# Eth_Switch.net
KiCad netlist of a schematic drawn in Altium Designer
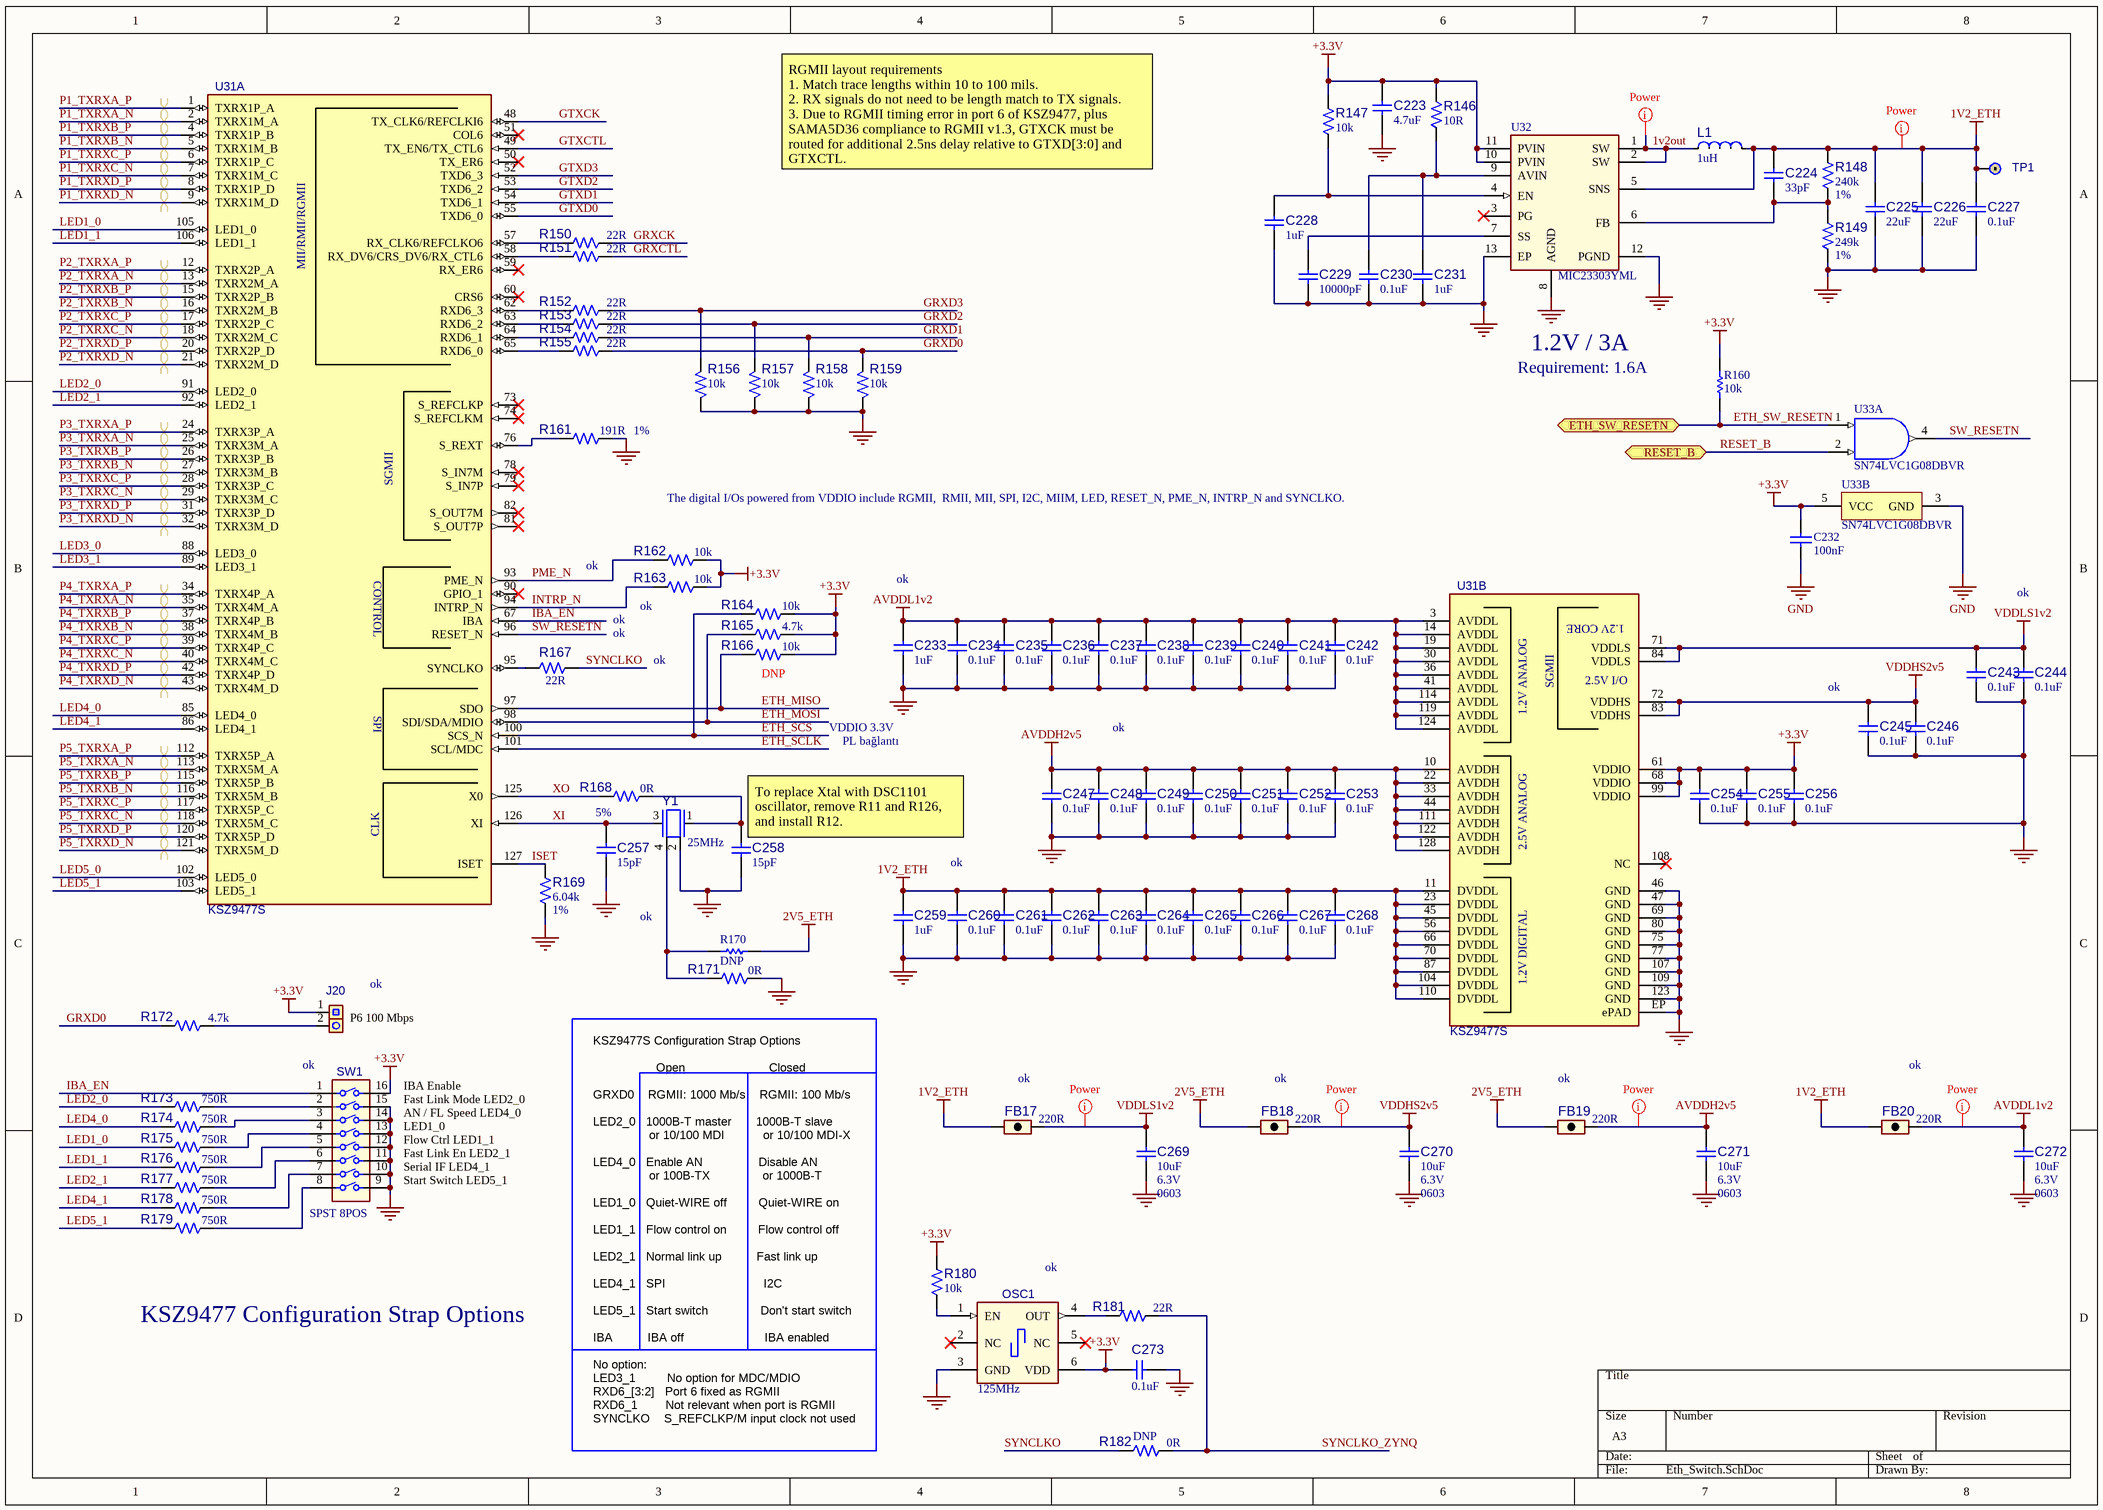
[diagram p0: Eth_Switch.SchDoc]

(export (version "E")
  (design (tool "Eeschema 10.0.6"))
  (components
    (comp (ref "C223")
      (value "4.7uF")
      (footprint "Ultrascale_PcbLib:CAP_C_0603")
      (description "Capacitor")
      (fields
        (field (name "VOLTAGE") "16V")
        (field (name "TOLERANCE") "10%")
        (field (name "OWNER") "Jairuz Agang-ang")
      )
      (libsource (lib "Ultrascale_SchLib") (part "Capacitor NP"))
    )
    (comp (ref "C224")
      (value "33pF")
      (footprint "Ultrascale_PcbLib:CAP_C_0603")
      (description "Capacitor")
      (fields (field (name "VOLTAGE") "50V") (field (name "TOLERANCE") "5%"))
      (libsource (lib "Ultrascale_SchLib") (part "Capacitor NP"))
    )
    (comp (ref "C225")
      (value "22uF")
      (footprint "Ultrascale_PcbLib:CAP_C_0805")
      (description "Capacitor")
      (fields (field (name "VOLTAGE") "16V") (field (name "TOLERANCE") "10%"))
      (libsource (lib "Ultrascale_SchLib") (part "Capacitor NP"))
    )
    (comp (ref "C226")
      (value "22uF")
      (footprint "Ultrascale_PcbLib:CAP_C_0805")
      (description "Capacitor")
      (fields (field (name "VOLTAGE") "16V") (field (name "TOLERANCE") "10%"))
      (libsource (lib "Ultrascale_SchLib") (part "Capacitor NP"))
    )
    (comp (ref "C227")
      (value "0.1uF")
      (footprint "Ultrascale_PcbLib:CAP_C_0402")
      (description "Capacitor")
      (fields
        (field (name "VOLTAGE") "50V")
        (field (name "TOLERANCE") "10%")
        (field (name "OWNER") "Jamus Griego")
      )
      (libsource (lib "Ultrascale_SchLib") (part "Capacitor NP"))
    )
    (comp (ref "C228")
      (value "1uF")
      (footprint "Ultrascale_PcbLib:CAP_C_0402")
      (description "Capacitor")
      (fields
        (field (name "VOLTAGE") "16V")
        (field (name "TOLERANCE") "10%")
        (field (name "OWNER") "Tad Ahlvers")
      )
      (libsource (lib "Ultrascale_SchLib") (part "Capacitor NP"))
    )
    (comp (ref "C229")
      (value "10000pF")
      (footprint "Ultrascale_PcbLib:CAP_C_0402")
      (description "Capacitor")
      (fields (field (name "VOLTAGE") "16V") (field (name "TOLERANCE") "10%"))
      (libsource (lib "Ultrascale_SchLib") (part "Capacitor NP"))
    )
    (comp (ref "C230")
      (value "0.1uF")
      (footprint "Ultrascale_PcbLib:CAP_C_0402")
      (description "Capacitor")
      (fields
        (field (name "VOLTAGE") "50V")
        (field (name "TOLERANCE") "10%")
        (field (name "OWNER") "Jamus Griego")
      )
      (libsource (lib "Ultrascale_SchLib") (part "Capacitor NP"))
    )
    (comp (ref "C231")
      (value "1uF")
      (footprint "Ultrascale_PcbLib:CAP_C_0402")
      (description "Capacitor")
      (fields
        (field (name "VOLTAGE") "16V")
        (field (name "TOLERANCE") "10%")
        (field (name "OWNER") "Tad Ahlvers")
      )
      (libsource (lib "Ultrascale_SchLib") (part "Capacitor NP"))
    )
    (comp (ref "C232")
      (value "100nF")
      (footprint "CAPC1005L_0402")
      (description "CAP CER 0.1UF 25V X7R 0402")
      (fields (field (name "VOLTAGE") "25V") (field (name "TOLERANCE") "10%"))
      (libsource (lib "Ultrascale_SchLib") (part "CAPCER0402X7R100N25V_10T"))
    )
    (comp (ref "C233")
      (value "1uF")
      (footprint "Ultrascale_PcbLib:CAP_C_0402")
      (description "Capacitor")
      (fields
        (field (name "VOLTAGE") "16V")
        (field (name "TOLERANCE") "10%")
        (field (name "OWNER") "Tad Ahlvers")
      )
      (libsource (lib "Ultrascale_SchLib") (part "Capacitor NP"))
    )
    (comp (ref "C234")
      (value "0.1uF")
      (footprint "Ultrascale_PcbLib:CAP_C_0402")
      (description "Capacitor")
      (fields
        (field (name "VOLTAGE") "50V")
        (field (name "TOLERANCE") "10%")
        (field (name "OWNER") "Jamus Griego")
      )
      (libsource (lib "Ultrascale_SchLib") (part "Capacitor NP"))
    )
    (comp (ref "C235")
      (value "0.1uF")
      (footprint "Ultrascale_PcbLib:CAP_C_0402")
      (description "Capacitor")
      (fields
        (field (name "VOLTAGE") "50V")
        (field (name "TOLERANCE") "10%")
        (field (name "OWNER") "Jamus Griego")
      )
      (libsource (lib "Ultrascale_SchLib") (part "Capacitor NP"))
    )
    (comp (ref "C236")
      (value "0.1uF")
      (footprint "Ultrascale_PcbLib:CAP_C_0402")
      (description "Capacitor")
      (fields
        (field (name "VOLTAGE") "50V")
        (field (name "TOLERANCE") "10%")
        (field (name "OWNER") "Jamus Griego")
      )
      (libsource (lib "Ultrascale_SchLib") (part "Capacitor NP"))
    )
    (comp (ref "C237")
      (value "0.1uF")
      (footprint "Ultrascale_PcbLib:CAP_C_0402")
      (description "Capacitor")
      (fields
        (field (name "VOLTAGE") "50V")
        (field (name "TOLERANCE") "10%")
        (field (name "OWNER") "Jamus Griego")
      )
      (libsource (lib "Ultrascale_SchLib") (part "Capacitor NP"))
    )
    (comp (ref "C238")
      (value "0.1uF")
      (footprint "Ultrascale_PcbLib:CAP_C_0402")
      (description "Capacitor")
      (fields
        (field (name "VOLTAGE") "50V")
        (field (name "TOLERANCE") "10%")
        (field (name "OWNER") "Jamus Griego")
      )
      (libsource (lib "Ultrascale_SchLib") (part "Capacitor NP"))
    )
    (comp (ref "C239")
      (value "0.1uF")
      (footprint "Ultrascale_PcbLib:CAP_C_0402")
      (description "Capacitor")
      (fields
        (field (name "VOLTAGE") "50V")
        (field (name "TOLERANCE") "10%")
        (field (name "OWNER") "Jamus Griego")
      )
      (libsource (lib "Ultrascale_SchLib") (part "Capacitor NP"))
    )
    (comp (ref "C240")
      (value "0.1uF")
      (footprint "Ultrascale_PcbLib:CAP_C_0402")
      (description "Capacitor")
      (fields
        (field (name "VOLTAGE") "50V")
        (field (name "TOLERANCE") "10%")
        (field (name "OWNER") "Jamus Griego")
      )
      (libsource (lib "Ultrascale_SchLib") (part "Capacitor NP"))
    )
    (comp (ref "C241")
      (value "0.1uF")
      (footprint "Ultrascale_PcbLib:CAP_C_0402")
      (description "Capacitor")
      (fields
        (field (name "VOLTAGE") "50V")
        (field (name "TOLERANCE") "10%")
        (field (name "OWNER") "Jamus Griego")
      )
      (libsource (lib "Ultrascale_SchLib") (part "Capacitor NP"))
    )
    (comp (ref "C242")
      (value "0.1uF")
      (footprint "Ultrascale_PcbLib:CAP_C_0402")
      (description "Capacitor")
      (fields
        (field (name "VOLTAGE") "50V")
        (field (name "TOLERANCE") "10%")
        (field (name "OWNER") "Jamus Griego")
      )
      (libsource (lib "Ultrascale_SchLib") (part "Capacitor NP"))
    )
    (comp (ref "C243")
      (value "0.1uF")
      (footprint "Ultrascale_PcbLib:CAP_C_0402")
      (description "Capacitor")
      (fields
        (field (name "VOLTAGE") "50V")
        (field (name "TOLERANCE") "10%")
        (field (name "OWNER") "Jamus Griego")
      )
      (libsource (lib "Ultrascale_SchLib") (part "Capacitor NP"))
    )
    (comp (ref "C244")
      (value "0.1uF")
      (footprint "Ultrascale_PcbLib:CAP_C_0402")
      (description "Capacitor")
      (fields
        (field (name "VOLTAGE") "50V")
        (field (name "TOLERANCE") "10%")
        (field (name "OWNER") "Jamus Griego")
      )
      (libsource (lib "Ultrascale_SchLib") (part "Capacitor NP"))
    )
    (comp (ref "C245")
      (value "0.1uF")
      (footprint "Ultrascale_PcbLib:CAP_C_0402")
      (description "Capacitor")
      (fields
        (field (name "VOLTAGE") "50V")
        (field (name "TOLERANCE") "10%")
        (field (name "OWNER") "Jamus Griego")
      )
      (libsource (lib "Ultrascale_SchLib") (part "Capacitor NP"))
    )
    (comp (ref "C246")
      (value "0.1uF")
      (footprint "Ultrascale_PcbLib:CAP_C_0402")
      (description "Capacitor")
      (fields
        (field (name "VOLTAGE") "50V")
        (field (name "TOLERANCE") "10%")
        (field (name "OWNER") "Jamus Griego")
      )
      (libsource (lib "Ultrascale_SchLib") (part "Capacitor NP"))
    )
    (comp (ref "C247")
      (value "0.1uF")
      (footprint "Ultrascale_PcbLib:CAP_C_0402")
      (description "Capacitor")
      (fields
        (field (name "VOLTAGE") "50V")
        (field (name "TOLERANCE") "10%")
        (field (name "OWNER") "Jamus Griego")
      )
      (libsource (lib "Ultrascale_SchLib") (part "Capacitor NP"))
    )
    (comp (ref "C248")
      (value "0.1uF")
      (footprint "Ultrascale_PcbLib:CAP_C_0402")
      (description "Capacitor")
      (fields
        (field (name "VOLTAGE") "50V")
        (field (name "TOLERANCE") "10%")
        (field (name "OWNER") "Jamus Griego")
      )
      (libsource (lib "Ultrascale_SchLib") (part "Capacitor NP"))
    )
    (comp (ref "C249")
      (value "0.1uF")
      (footprint "Ultrascale_PcbLib:CAP_C_0402")
      (description "Capacitor")
      (fields
        (field (name "VOLTAGE") "50V")
        (field (name "TOLERANCE") "10%")
        (field (name "OWNER") "Jamus Griego")
      )
      (libsource (lib "Ultrascale_SchLib") (part "Capacitor NP"))
    )
    (comp (ref "C250")
      (value "0.1uF")
      (footprint "Ultrascale_PcbLib:CAP_C_0402")
      (description "Capacitor")
      (fields
        (field (name "VOLTAGE") "50V")
        (field (name "TOLERANCE") "10%")
        (field (name "OWNER") "Jamus Griego")
      )
      (libsource (lib "Ultrascale_SchLib") (part "Capacitor NP"))
    )
    (comp (ref "C251")
      (value "0.1uF")
      (footprint "Ultrascale_PcbLib:CAP_C_0402")
      (description "Capacitor")
      (fields
        (field (name "VOLTAGE") "50V")
        (field (name "TOLERANCE") "10%")
        (field (name "OWNER") "Jamus Griego")
      )
      (libsource (lib "Ultrascale_SchLib") (part "Capacitor NP"))
    )
    (comp (ref "C252")
      (value "0.1uF")
      (footprint "Ultrascale_PcbLib:CAP_C_0402")
      (description "Capacitor")
      (fields
        (field (name "VOLTAGE") "50V")
        (field (name "TOLERANCE") "10%")
        (field (name "OWNER") "Jamus Griego")
      )
      (libsource (lib "Ultrascale_SchLib") (part "Capacitor NP"))
    )
    (comp (ref "C253")
      (value "0.1uF")
      (footprint "Ultrascale_PcbLib:CAP_C_0402")
      (description "Capacitor")
      (fields
        (field (name "VOLTAGE") "50V")
        (field (name "TOLERANCE") "10%")
        (field (name "OWNER") "Jamus Griego")
      )
      (libsource (lib "Ultrascale_SchLib") (part "Capacitor NP"))
    )
    (comp (ref "C254")
      (value "0.1uF")
      (footprint "Ultrascale_PcbLib:CAP_C_0402")
      (description "Capacitor")
      (fields
        (field (name "VOLTAGE") "50V")
        (field (name "TOLERANCE") "10%")
        (field (name "OWNER") "Jamus Griego")
      )
      (libsource (lib "Ultrascale_SchLib") (part "Capacitor NP"))
    )
    (comp (ref "C255")
      (value "0.1uF")
      (footprint "Ultrascale_PcbLib:CAP_C_0402")
      (description "Capacitor")
      (fields
        (field (name "VOLTAGE") "50V")
        (field (name "TOLERANCE") "10%")
        (field (name "OWNER") "Jamus Griego")
      )
      (libsource (lib "Ultrascale_SchLib") (part "Capacitor NP"))
    )
    (comp (ref "C256")
      (value "0.1uF")
      (footprint "Ultrascale_PcbLib:CAP_C_0402")
      (description "Capacitor")
      (fields
        (field (name "VOLTAGE") "50V")
        (field (name "TOLERANCE") "10%")
        (field (name "OWNER") "Jamus Griego")
      )
      (libsource (lib "Ultrascale_SchLib") (part "Capacitor NP"))
    )
    (comp (ref "C257")
      (value "15pF")
      (footprint "Ultrascale_PcbLib:CAP_C_0402")
      (description "Capacitor")
      (fields
        (field (name "VOLTAGE") "50V")
        (field (name "TOLERANCE") "5%")
        (field (name "Comment") "Capacitor NP")
      )
      (libsource (lib "Ultrascale_SchLib") (part "Capacitor NP"))
    )
    (comp (ref "C258")
      (value "15pF")
      (footprint "Ultrascale_PcbLib:CAP_C_0402")
      (description "Capacitor")
      (fields (field (name "VOLTAGE") "50V") (field (name "TOLERANCE") "5%"))
      (libsource (lib "Ultrascale_SchLib") (part "Capacitor NP"))
    )
    (comp (ref "C259")
      (value "1uF")
      (footprint "Ultrascale_PcbLib:CAP_C_0402")
      (description "Capacitor")
      (fields
        (field (name "VOLTAGE") "16V")
        (field (name "TOLERANCE") "10%")
        (field (name "OWNER") "Tad Ahlvers")
      )
      (libsource (lib "Ultrascale_SchLib") (part "Capacitor NP"))
    )
    (comp (ref "C260")
      (value "0.1uF")
      (footprint "Ultrascale_PcbLib:CAP_C_0402")
      (description "Capacitor")
      (fields
        (field (name "VOLTAGE") "50V")
        (field (name "TOLERANCE") "10%")
        (field (name "OWNER") "Jamus Griego")
      )
      (libsource (lib "Ultrascale_SchLib") (part "Capacitor NP"))
    )
    (comp (ref "C261")
      (value "0.1uF")
      (footprint "Ultrascale_PcbLib:CAP_C_0402")
      (description "Capacitor")
      (fields
        (field (name "VOLTAGE") "50V")
        (field (name "TOLERANCE") "10%")
        (field (name "OWNER") "Jamus Griego")
      )
      (libsource (lib "Ultrascale_SchLib") (part "Capacitor NP"))
    )
    (comp (ref "C262")
      (value "0.1uF")
      (footprint "Ultrascale_PcbLib:CAP_C_0402")
      (description "Capacitor")
      (fields
        (field (name "VOLTAGE") "50V")
        (field (name "TOLERANCE") "10%")
        (field (name "OWNER") "Jamus Griego")
      )
      (libsource (lib "Ultrascale_SchLib") (part "Capacitor NP"))
    )
    (comp (ref "C263")
      (value "0.1uF")
      (footprint "Ultrascale_PcbLib:CAP_C_0402")
      (description "Capacitor")
      (fields
        (field (name "VOLTAGE") "50V")
        (field (name "TOLERANCE") "10%")
        (field (name "OWNER") "Jamus Griego")
      )
      (libsource (lib "Ultrascale_SchLib") (part "Capacitor NP"))
    )
    (comp (ref "C264")
      (value "0.1uF")
      (footprint "Ultrascale_PcbLib:CAP_C_0402")
      (description "Capacitor")
      (fields
        (field (name "VOLTAGE") "50V")
        (field (name "TOLERANCE") "10%")
        (field (name "OWNER") "Jamus Griego")
      )
      (libsource (lib "Ultrascale_SchLib") (part "Capacitor NP"))
    )
    (comp (ref "C265")
      (value "0.1uF")
      (footprint "Ultrascale_PcbLib:CAP_C_0402")
      (description "Capacitor")
      (fields
        (field (name "VOLTAGE") "50V")
        (field (name "TOLERANCE") "10%")
        (field (name "OWNER") "Jamus Griego")
      )
      (libsource (lib "Ultrascale_SchLib") (part "Capacitor NP"))
    )
    (comp (ref "C266")
      (value "0.1uF")
      (footprint "Ultrascale_PcbLib:CAP_C_0402")
      (description "Capacitor")
      (fields
        (field (name "VOLTAGE") "50V")
        (field (name "TOLERANCE") "10%")
        (field (name "OWNER") "Jamus Griego")
      )
      (libsource (lib "Ultrascale_SchLib") (part "Capacitor NP"))
    )
    (comp (ref "C267")
      (value "0.1uF")
      (footprint "Ultrascale_PcbLib:CAP_C_0402")
      (description "Capacitor")
      (fields
        (field (name "VOLTAGE") "50V")
        (field (name "TOLERANCE") "10%")
        (field (name "OWNER") "Jamus Griego")
      )
      (libsource (lib "Ultrascale_SchLib") (part "Capacitor NP"))
    )
    (comp (ref "C268")
      (value "0.1uF")
      (footprint "Ultrascale_PcbLib:CAP_C_0402")
      (description "Capacitor")
      (fields
        (field (name "VOLTAGE") "50V")
        (field (name "TOLERANCE") "10%")
        (field (name "OWNER") "Jamus Griego")
      )
      (libsource (lib "Ultrascale_SchLib") (part "Capacitor NP"))
    )
    (comp (ref "C269")
      (value "10uF")
      (footprint "Ultrascale_PcbLib:CAP_C_0603")
      (description "Capacitor")
      (fields
        (field (name "VOLTAGE") "6.3V")
        (field (name "PACKAGE") "0603")
        (field (name "TOLERANCE") "20%")
        (field (name "Comment") "Capacitor NP")
      )
      (libsource (lib "Ultrascale_SchLib") (part "Capacitor NP"))
    )
    (comp (ref "C270")
      (value "10uF")
      (footprint "Ultrascale_PcbLib:CAP_C_0603")
      (description "Capacitor")
      (fields
        (field (name "VOLTAGE") "6.3V")
        (field (name "PACKAGE") "0603")
        (field (name "TOLERANCE") "20%")
        (field (name "Comment") "Capacitor NP")
      )
      (libsource (lib "Ultrascale_SchLib") (part "Capacitor NP"))
    )
    (comp (ref "C271")
      (value "10uF")
      (footprint "Ultrascale_PcbLib:CAP_C_0603")
      (description "Capacitor")
      (fields
        (field (name "VOLTAGE") "6.3V")
        (field (name "PACKAGE") "0603")
        (field (name "TOLERANCE") "20%")
        (field (name "Comment") "Capacitor NP")
      )
      (libsource (lib "Ultrascale_SchLib") (part "Capacitor NP"))
    )
    (comp (ref "C272")
      (value "10uF")
      (footprint "Ultrascale_PcbLib:CAP_C_0603")
      (description "Capacitor")
      (fields
        (field (name "VOLTAGE") "6.3V")
        (field (name "PACKAGE") "0603")
        (field (name "TOLERANCE") "20%")
        (field (name "Comment") "Capacitor NP")
      )
      (libsource (lib "Ultrascale_SchLib") (part "Capacitor NP"))
    )
    (comp (ref "C273")
      (value "0.1uF")
      (footprint "Ultrascale_PcbLib:CAP_C_0402")
      (description "Capacitor")
      (fields
        (field (name "VOLTAGE") "50V")
        (field (name "TOLERANCE") "10%")
        (field (name "OWNER") "Jamus Griego")
      )
      (libsource (lib "Ultrascale_SchLib") (part "Capacitor NP"))
    )
    (comp (ref "FB17")
      (value "220R")
      (footprint "Ultrascale_PcbLib:IND_C_0603")
      (fields (field (name "Comment") "Ferrite Bead") (field (name "OWNER") "Razvan Cristescu"))
      (libsource (lib "Ultrascale_SchLib") (part "Ferrite Bead"))
    )
    (comp (ref "FB18")
      (value "220R")
      (footprint "Ultrascale_PcbLib:IND_C_0603")
      (fields (field (name "Comment") "Ferrite Bead") (field (name "OWNER") "Razvan Cristescu"))
      (libsource (lib "Ultrascale_SchLib") (part "Ferrite Bead"))
    )
    (comp (ref "FB19")
      (value "220R")
      (footprint "Ultrascale_PcbLib:IND_C_0603")
      (fields (field (name "Comment") "Ferrite Bead") (field (name "OWNER") "Razvan Cristescu"))
      (libsource (lib "Ultrascale_SchLib") (part "Ferrite Bead"))
    )
    (comp (ref "FB20")
      (value "220R")
      (footprint "Ultrascale_PcbLib:IND_C_0603")
      (fields (field (name "Comment") "Ferrite Bead") (field (name "OWNER") "Razvan Cristescu"))
      (libsource (lib "Ultrascale_SchLib") (part "Ferrite Bead"))
    )
    (comp (ref "J20")
      (value "HDR-2.54 Male 1x2")
      (footprint "Ultrascale_PcbLib:HDR_M_2.54_1x2")
      (description "CONN HEADER 2POS .100\" SGL GOLD")
      (fields
        (field (name "PART CHECKED") "Jennifer Hancock")
        (field (name "PART 3D MODEL CHECKED") "Jennifer Hancock")
        (field (name "OWNER") "*")
      )
      (libsource (lib "Ultrascale_SchLib") (part "Header 1x2"))
    )
    (comp (ref "L1")
      (value "1uH")
      (footprint "Ultrascale_PcbLib:IND_TAI_NR_L3W3H1.5")
      (description "Inductor")
      (fields (field (name "OWNER") "Tad Ahlvers"))
      (libsource (lib "Ultrascale_SchLib") (part "Inductor"))
    )
    (comp (ref "OSC1")
      (value "~")
      (footprint "Ultrascale_PcbLib:OSC_5MX3M2_A")
      (description "OSC MEMS 125.000MHZ CMOS SMD")
      (fields (field (name "FREQUENCY") "125MHz"))
      (libsource (lib "Ultrascale_SchLib") (part "DSC1101B12-125.0000"))
    )
    (comp (ref "R146")
      (value "10R")
      (footprint "Ultrascale_PcbLib:RES_C_0603")
      (description "Resistor")
      (fields
        (field (name "TOLERANCE") "1%")
        (field (name "VOLTAGE") "50V")
        (field (name "OWNER") "Aaron VanDuerm")
      )
      (libsource (lib "Ultrascale_SchLib") (part "Resistor"))
    )
    (comp (ref "R147")
      (value "10k")
      (footprint "Ultrascale_PcbLib:RES_C_0603")
      (description "Resistor")
      (fields (field (name "TOLERANCE") "1%") (field (name "POWER") "1/10W"))
      (libsource (lib "Ultrascale_SchLib") (part "Resistor"))
    )
    (comp (ref "R148")
      (value "240k")
      (footprint "Ultrascale_PcbLib:RES_C_0603")
      (description "Resistor")
      (fields
        (field (name "TOLERANCE") "1%")
        (field (name "VOLTAGE") "75V")
        (field (name "POWER") "1/10W")
        (field (name "OWNER") "Tad Ahlvers")
      )
      (libsource (lib "Ultrascale_SchLib") (part "Resistor"))
    )
    (comp (ref "R149")
      (value "249k")
      (footprint "Ultrascale_PcbLib:RES_C_0603")
      (description "Resistor")
      (fields (field (name "TOLERANCE") "1%") (field (name "VOLTAGE") "75V") (field (name "POWER") "1/10W"))
      (libsource (lib "Ultrascale_SchLib") (part "Resistor"))
    )
    (comp (ref "R150")
      (value "22R")
      (footprint "Ultrascale_PcbLib:RES_C_0603")
      (description "Resistor")
      (fields (field (name "TOLERANCE") "1%") (field (name "VOLTAGE") "50V"))
      (libsource (lib "Ultrascale_SchLib") (part "Resistor"))
    )
    (comp (ref "R151")
      (value "22R")
      (footprint "Ultrascale_PcbLib:RES_C_0603")
      (description "Resistor")
      (fields (field (name "TOLERANCE") "1%") (field (name "VOLTAGE") "50V"))
      (libsource (lib "Ultrascale_SchLib") (part "Resistor"))
    )
    (comp (ref "R152")
      (value "22R")
      (footprint "Ultrascale_PcbLib:RES_C_0603")
      (description "Resistor")
      (fields (field (name "TOLERANCE") "1%") (field (name "VOLTAGE") "50V"))
      (libsource (lib "Ultrascale_SchLib") (part "Resistor"))
    )
    (comp (ref "R153")
      (value "22R")
      (footprint "Ultrascale_PcbLib:RES_C_0603")
      (description "Resistor")
      (fields (field (name "TOLERANCE") "1%") (field (name "VOLTAGE") "50V"))
      (libsource (lib "Ultrascale_SchLib") (part "Resistor"))
    )
    (comp (ref "R154")
      (value "22R")
      (footprint "Ultrascale_PcbLib:RES_C_0603")
      (description "Resistor")
      (fields (field (name "TOLERANCE") "1%") (field (name "VOLTAGE") "50V"))
      (libsource (lib "Ultrascale_SchLib") (part "Resistor"))
    )
    (comp (ref "R155")
      (value "22R")
      (footprint "Ultrascale_PcbLib:RES_C_0603")
      (description "Resistor")
      (fields (field (name "TOLERANCE") "1%") (field (name "VOLTAGE") "50V"))
      (libsource (lib "Ultrascale_SchLib") (part "Resistor"))
    )
    (comp (ref "R156")
      (value "10k")
      (footprint "Ultrascale_PcbLib:RES_C_0603")
      (description "Resistor")
      (fields (field (name "TOLERANCE") "1%") (field (name "POWER") "1/10W"))
      (libsource (lib "Ultrascale_SchLib") (part "Resistor"))
    )
    (comp (ref "R157")
      (value "10k")
      (footprint "Ultrascale_PcbLib:RES_C_0603")
      (description "Resistor")
      (fields (field (name "TOLERANCE") "1%") (field (name "POWER") "1/10W"))
      (libsource (lib "Ultrascale_SchLib") (part "Resistor"))
    )
    (comp (ref "R158")
      (value "10k")
      (footprint "Ultrascale_PcbLib:RES_C_0603")
      (description "Resistor")
      (fields (field (name "TOLERANCE") "1%") (field (name "POWER") "1/10W"))
      (libsource (lib "Ultrascale_SchLib") (part "Resistor"))
    )
    (comp (ref "R159")
      (value "10k")
      (footprint "Ultrascale_PcbLib:RES_C_0603")
      (description "Resistor")
      (fields (field (name "TOLERANCE") "1%") (field (name "POWER") "1/10W"))
      (libsource (lib "Ultrascale_SchLib") (part "Resistor"))
    )
    (comp (ref "R160")
      (value "10k")
      (footprint "RESC1005L_0402")
      (description "RES SMD 10K OHM 0.5% 1/16W 0402")
      (fields (field (name "POWER") "1/16W") (field (name "TOLERANCE") "0.5%"))
      (libsource (lib "Ultrascale_SchLib") (part "RES0402_10K_0W1_05T"))
    )
    (comp (ref "R161")
      (value "191R")
      (footprint "Ultrascale_PcbLib:RES_C_0603")
      (description "Resistor")
      (fields
        (field (name "TOLERANCE") "1%")
        (field (name "POWER") "1/10W")
        (field (name "OWNER") "Sam Charles")
      )
      (libsource (lib "Ultrascale_SchLib") (part "Resistor"))
    )
    (comp (ref "R162")
      (value "10k")
      (footprint "Ultrascale_PcbLib:RES_C_0603")
      (description "Resistor")
      (fields (field (name "TOLERANCE") "1%") (field (name "POWER") "1/10W"))
      (libsource (lib "Ultrascale_SchLib") (part "Resistor"))
    )
    (comp (ref "R163")
      (value "10k")
      (footprint "Ultrascale_PcbLib:RES_C_0603")
      (description "Resistor")
      (fields (field (name "TOLERANCE") "1%") (field (name "POWER") "1/10W"))
      (libsource (lib "Ultrascale_SchLib") (part "Resistor"))
    )
    (comp (ref "R164")
      (value "10k")
      (footprint "Ultrascale_PcbLib:RES_C_0603")
      (description "Resistor")
      (fields (field (name "TOLERANCE") "1%") (field (name "POWER") "1/10W"))
      (libsource (lib "Ultrascale_SchLib") (part "Resistor"))
    )
    (comp (ref "R165")
      (value "4.7k")
      (footprint "Ultrascale_PcbLib:RES_C_0603")
      (description "Resistor")
      (fields (field (name "TOLERANCE") "1%") (field (name "VOLTAGE") "50V"))
      (libsource (lib "Ultrascale_SchLib") (part "Resistor"))
    )
    (comp (ref "R166")
      (value "10k")
      (footprint "Ultrascale_PcbLib:RES_C_0603")
      (description "Resistor")
      (fields (field (name "TOLERANCE") "1%") (field (name "POWER") "1/10W") (field (name "POPULATED") "DNP"))
      (libsource (lib "Ultrascale_SchLib") (part "Resistor"))
    )
    (comp (ref "R167")
      (value "22R")
      (footprint "Ultrascale_PcbLib:RES_C_0603")
      (description "Resistor")
      (fields (field (name "TOLERANCE") "1%") (field (name "VOLTAGE") "50V"))
      (libsource (lib "Ultrascale_SchLib") (part "Resistor"))
    )
    (comp (ref "R168")
      (value "0R")
      (footprint "Ultrascale_PcbLib:RES_C_0603")
      (description "Resistor")
      (fields (field (name "POWER") "1/10W"))
      (libsource (lib "Ultrascale_SchLib") (part "Resistor"))
    )
    (comp (ref "R169")
      (value "6.04k")
      (footprint "Ultrascale_PcbLib:RES_C_0603")
      (description "Resistor")
      (fields (field (name "TOLERANCE") "1%") (field (name "VOLTAGE") "50V") (field (name "POWER") "1/10W"))
      (libsource (lib "Ultrascale_SchLib") (part "Resistor"))
    )
    (comp (ref "R170")
      (value "DNP")
      (footprint "RESC1005L_0402")
      (description "RES SMD 0402 Footprint")
      (fields (field (name "Comment") "RES0402"))
      (libsource (lib "Ultrascale_SchLib") (part "RES0402"))
    )
    (comp (ref "R171")
      (value "0R")
      (footprint "Ultrascale_PcbLib:RES_C_0603")
      (description "Resistor")
      (fields (field (name "POWER") "1/10W"))
      (libsource (lib "Ultrascale_SchLib") (part "Resistor"))
    )
    (comp (ref "R172")
      (value "4.7k")
      (footprint "Ultrascale_PcbLib:RES_C_0603")
      (description "Resistor")
      (fields (field (name "TOLERANCE") "1%") (field (name "VOLTAGE") "50V"))
      (libsource (lib "Ultrascale_SchLib") (part "Resistor"))
    )
    (comp (ref "R173")
      (value "750R")
      (footprint "Ultrascale_PcbLib:RES_C_0603")
      (description "Resistor")
      (fields
        (field (name "TOLERANCE") "1%")
        (field (name "VOLTAGE") "75V")
        (field (name "OWNER") "Tad Ahlvers")
      )
      (libsource (lib "Ultrascale_SchLib") (part "Resistor"))
    )
    (comp (ref "R174")
      (value "750R")
      (footprint "Ultrascale_PcbLib:RES_C_0603")
      (description "Resistor")
      (fields
        (field (name "TOLERANCE") "1%")
        (field (name "VOLTAGE") "75V")
        (field (name "OWNER") "Tad Ahlvers")
      )
      (libsource (lib "Ultrascale_SchLib") (part "Resistor"))
    )
    (comp (ref "R175")
      (value "750R")
      (footprint "Ultrascale_PcbLib:RES_C_0603")
      (description "Resistor")
      (fields
        (field (name "TOLERANCE") "1%")
        (field (name "VOLTAGE") "75V")
        (field (name "OWNER") "Tad Ahlvers")
      )
      (libsource (lib "Ultrascale_SchLib") (part "Resistor"))
    )
    (comp (ref "R176")
      (value "750R")
      (footprint "Ultrascale_PcbLib:RES_C_0603")
      (description "Resistor")
      (fields
        (field (name "TOLERANCE") "1%")
        (field (name "VOLTAGE") "75V")
        (field (name "OWNER") "Tad Ahlvers")
      )
      (libsource (lib "Ultrascale_SchLib") (part "Resistor"))
    )
    (comp (ref "R177")
      (value "750R")
      (footprint "Ultrascale_PcbLib:RES_C_0603")
      (description "Resistor")
      (fields
        (field (name "TOLERANCE") "1%")
        (field (name "VOLTAGE") "75V")
        (field (name "OWNER") "Tad Ahlvers")
      )
      (libsource (lib "Ultrascale_SchLib") (part "Resistor"))
    )
    (comp (ref "R178")
      (value "750R")
      (footprint "Ultrascale_PcbLib:RES_C_0603")
      (description "Resistor")
      (fields
        (field (name "TOLERANCE") "1%")
        (field (name "VOLTAGE") "75V")
        (field (name "OWNER") "Tad Ahlvers")
      )
      (libsource (lib "Ultrascale_SchLib") (part "Resistor"))
    )
    (comp (ref "R179")
      (value "750R")
      (footprint "Ultrascale_PcbLib:RES_C_0603")
      (description "Resistor")
      (fields
        (field (name "TOLERANCE") "1%")
        (field (name "VOLTAGE") "75V")
        (field (name "OWNER") "Tad Ahlvers")
      )
      (libsource (lib "Ultrascale_SchLib") (part "Resistor"))
    )
    (comp (ref "R180")
      (value "10k")
      (footprint "Ultrascale_PcbLib:RES_C_0603")
      (description "Resistor")
      (fields (field (name "TOLERANCE") "1%") (field (name "POWER") "1/10W"))
      (libsource (lib "Ultrascale_SchLib") (part "Resistor"))
    )
    (comp (ref "R181")
      (value "22R")
      (footprint "Ultrascale_PcbLib:RES_C_0603")
      (description "Resistor")
      (fields (field (name "TOLERANCE") "1%") (field (name "VOLTAGE") "50V"))
      (libsource (lib "Ultrascale_SchLib") (part "Resistor"))
    )
    (comp (ref "R182")
      (value "0R")
      (footprint "Ultrascale_PcbLib:RES_C_0603")
      (description "Resistor")
      (fields (field (name "POWER") "1/10W") (field (name "POPULATED") "DNP"))
      (libsource (lib "Ultrascale_SchLib") (part "Resistor"))
    )
    (comp (ref "SW1")
      (value "SPST 8POS")
      (footprint "Ultrascale_PcbLib:SW_SM_8POS24V_TE")
      (description "Switch DIP SPST 8POS SMD")
      (libsource (lib "Ultrascale_SchLib") (part "Switch DIP 8 Pos"))
    )
    (comp (ref "TP1")
      (value "Jumper")
      (footprint "Ultrascale_PcbLib:TP_PAD51D36")
      (description "Test Pad TH 51X36")
      (fields (field (name "MANUFACTURER PART NUMBER") "none"))
      (libsource (lib "Ultrascale_SchLib") (part "TEST PAD TH 51X36"))
    )
    (comp (ref "U31")
      (value "KSZ9477S")
      (footprint "TQFP-128_14x14_EP10x10")
      (description "IC, 7-Port Gigabit Ethernet Switch with 2 RGMII / MII / RMII Interfaces, TQFP128")
      (fields (field (name "OWNER") "sam charles"))
      (libsource (lib "Ultrascale_SchLib") (part "KSZ9477S_TQFP128"))
    )
    (comp (ref "U32")
      (value "MIC23303YML")
      (footprint "Ultrascale_PcbLib:DFN-12_3x3")
      (description "4MHz PWM 3A Buck Regulator with HyperLight Load and Power Good")
      (fields (field (name "OWNER") "*") (field (name "PART CHECKED") "Carl Johnson"))
      (libsource (lib "Ultrascale_SchLib") (part "MIC23303YML"))
    )
    (comp (ref "U33")
      (value "SN74LVC1G08DBVR")
      (footprint "DBV0005A_N")
      (description "Single 2-Input Positive-AND Gate, DBV0005A, LARGE T&R")
      (fields (field (name "GENERIC PART NUMBER") "SN74LVC1G08"))
      (libsource (lib "Ultrascale_SchLib") (part "SN74LVC1G08DBVR"))
    )
    (comp (ref "Y1")
      (value "XTAL 25MHz 4 pins 3225")
      (footprint "Ultrascale_PcbLib:XTAL_4PIN_3M2X2M5")
      (description "Crystal 25MHz 4 pins 3225")
      (fields (field (name "FREQUENCY") "25MHz"))
      (libsource (lib "Ultrascale_SchLib") (part "XTAL 25MHz 4 pins 3225"))
    )
  )
  (nets
    (net (code "1") (name "+3.3V") (class "Default")
      (node (ref "C223") (pin "2") (pinfunction "2_2") (pintype "passive"))
      (node (ref "C232") (pin "1") (pinfunction "1_1") (pintype "passive"))
      (node (ref "C254") (pin "2") (pinfunction "2_2") (pintype "passive"))
      (node (ref "C255") (pin "2") (pinfunction "2_2") (pintype "passive"))
      (node (ref "C256") (pin "2") (pinfunction "2_2") (pintype "passive"))
      (node (ref "C273") (pin "2") (pinfunction "2_2") (pintype "passive"))
      (node (ref "J20") (pin "1") (pinfunction "P1_1") (pintype "passive"))
      (node (ref "OSC1") (pin "6") (pinfunction "VDD_6") (pintype "power_in"))
      (node (ref "R146") (pin "2") (pinfunction "2_2") (pintype "passive"))
      (node (ref "R147") (pin "2") (pinfunction "2_2") (pintype "passive"))
      (node (ref "R160") (pin "2") (pinfunction "2_2") (pintype "passive"))
      (node (ref "R162") (pin "1") (pinfunction "1_1") (pintype "passive"))
      (node (ref "R163") (pin "1") (pinfunction "1_1") (pintype "passive"))
      (node (ref "R164") (pin "1") (pinfunction "1_1") (pintype "passive"))
      (node (ref "R165") (pin "1") (pinfunction "1_1") (pintype "passive"))
      (node (ref "R166") (pin "1") (pinfunction "1_1") (pintype "passive"))
      (node (ref "R180") (pin "2") (pinfunction "2_2") (pintype "passive"))
      (node (ref "SW1") (pin "16") (pinfunction "16_16") (pintype "passive"))
      (node (ref "U31") (pin "61") (pinfunction "VDDIO_61") (pintype "power_in"))
      (node (ref "U31") (pin "68") (pinfunction "VDDIO_68") (pintype "power_in"))
      (node (ref "U31") (pin "99") (pinfunction "VDDIO_99") (pintype "power_in"))
      (node (ref "U32") (pin "10") (pinfunction "PVIN_10") (pintype "power_in"))
      (node (ref "U32") (pin "11") (pinfunction "PVIN_11") (pintype "power_in"))
      (node (ref "U33") (pin "5") (pinfunction "VCC_5") (pintype "power_in"))
    )
    (net (code "2") (name "/1v2out") (class "Default")
      (node (ref "L1") (pin "1") (pinfunction "S_1") (pintype "passive"))
      (node (ref "U32") (pin "1") (pinfunction "SW_1") (pintype "passive"))
      (node (ref "U32") (pin "2") (pinfunction "SW_2") (pintype "passive"))
    )
    (net (code "3") (name "/ETH_MISO") (class "Default")
      (node (ref "R166") (pin "2") (pinfunction "2_2") (pintype "passive"))
      (node (ref "U31") (pin "97") (pinfunction "SDO_97") (pintype "output"))
    )
    (net (code "4") (name "/ETH_MOSI") (class "Default")
      (node (ref "R165") (pin "2") (pinfunction "2_2") (pintype "passive"))
      (node (ref "U31") (pin "98") (pinfunction "SDI/SDA/MDIO_98") (pintype "bidirectional"))
    )
    (net (code "5") (name "/ETH_SCLK") (class "Default")
      (node (ref "U31") (pin "101") (pinfunction "SCL/MDC_101") (pintype "input"))
    )
    (net (code "6") (name "/ETH_SCS") (class "Default")
      (node (ref "R164") (pin "2") (pinfunction "2_2") (pintype "passive"))
      (node (ref "U31") (pin "100") (pinfunction "SCS_N_100") (pintype "input"))
    )
    (net (code "7") (name "/ETH_SW_RESETN") (class "Default")
      (node (ref "R160") (pin "1") (pinfunction "1_1") (pintype "passive"))
      (node (ref "U33") (pin "1") (pinfunction "A_1") (pintype "input"))
    )
    (net (code "8") (name "/GRXCK") (class "Default")
      (node (ref "R150") (pin "2") (pinfunction "2_2") (pintype "passive"))
    )
    (net (code "9") (name "/GRXCTL") (class "Default")
      (node (ref "R151") (pin "2") (pinfunction "2_2") (pintype "passive"))
    )
    (net (code "10") (name "/GRXD0") (class "Default")
      (node (ref "R155") (pin "2") (pinfunction "2_2") (pintype "passive"))
      (node (ref "R159") (pin "1") (pinfunction "1_1") (pintype "passive"))
      (node (ref "R172") (pin "1") (pinfunction "1_1") (pintype "passive"))
    )
    (net (code "11") (name "/GRXD1") (class "Default")
      (node (ref "R154") (pin "2") (pinfunction "2_2") (pintype "passive"))
      (node (ref "R158") (pin "1") (pinfunction "1_1") (pintype "passive"))
    )
    (net (code "12") (name "/GRXD2") (class "Default")
      (node (ref "R153") (pin "2") (pinfunction "2_2") (pintype "passive"))
      (node (ref "R157") (pin "1") (pinfunction "1_1") (pintype "passive"))
    )
    (net (code "13") (name "/GRXD3") (class "Default")
      (node (ref "R152") (pin "2") (pinfunction "2_2") (pintype "passive"))
      (node (ref "R156") (pin "1") (pinfunction "1_1") (pintype "passive"))
    )
    (net (code "14") (name "/GTXCK") (class "Default")
      (node (ref "U31") (pin "48") (pinfunction "TX_CLK6/REFCLKI6_48") (pintype "bidirectional"))
    )
    (net (code "15") (name "/GTXCTL") (class "Default")
      (node (ref "U31") (pin "49") (pinfunction "TX_EN6/TX_CTL6_49") (pintype "input"))
    )
    (net (code "16") (name "/GTXD0") (class "Default")
      (node (ref "U31") (pin "55") (pinfunction "TXD6_0_55") (pintype "bidirectional"))
    )
    (net (code "17") (name "/GTXD1") (class "Default")
      (node (ref "U31") (pin "54") (pinfunction "TXD6_1_54") (pintype "input"))
    )
    (net (code "18") (name "/GTXD2") (class "Default")
      (node (ref "U31") (pin "53") (pinfunction "TXD6_2_53") (pintype "input"))
    )
    (net (code "19") (name "/GTXD3") (class "Default")
      (node (ref "U31") (pin "52") (pinfunction "TXD6_3_52") (pintype "input"))
    )
    (net (code "20") (name "/IBA_EN") (class "Default")
      (node (ref "SW1") (pin "1") (pinfunction "1_1") (pintype "passive"))
      (node (ref "U31") (pin "67") (pinfunction "IBA_67") (pintype "input"))
    )
    (net (code "21") (name "/INTRP_N") (class "Default")
      (node (ref "R163") (pin "2") (pinfunction "2_2") (pintype "passive"))
      (node (ref "U31") (pin "94") (pinfunction "INTRP_N_94") (pintype "output"))
    )
    (net (code "22") (name "/ISET") (class "Default")
      (node (ref "R169") (pin "2") (pinfunction "2_2") (pintype "passive"))
      (node (ref "U31") (pin "127") (pinfunction "ISET_127") (pintype "passive"))
    )
    (net (code "23") (name "/LED1_0") (class "Default")
      (node (ref "R175") (pin "1") (pinfunction "1_1") (pintype "passive"))
      (node (ref "U31") (pin "105") (pinfunction "LED1_0_105") (pintype "bidirectional"))
    )
    (net (code "24") (name "/LED1_1") (class "Default")
      (node (ref "R176") (pin "1") (pinfunction "1_1") (pintype "passive"))
      (node (ref "U31") (pin "106") (pinfunction "LED1_1_106") (pintype "bidirectional"))
    )
    (net (code "25") (name "/LED2_0") (class "Default")
      (node (ref "R173") (pin "1") (pinfunction "1_1") (pintype "passive"))
      (node (ref "U31") (pin "91") (pinfunction "LED2_0_91") (pintype "bidirectional"))
    )
    (net (code "26") (name "/LED2_1") (class "Default")
      (node (ref "R177") (pin "1") (pinfunction "1_1") (pintype "passive"))
      (node (ref "U31") (pin "92") (pinfunction "LED2_1_92") (pintype "bidirectional"))
    )
    (net (code "27") (name "/LED3_0") (class "Default")
      (node (ref "U31") (pin "88") (pinfunction "LED3_0_88") (pintype "bidirectional"))
    )
    (net (code "28") (name "/LED3_1") (class "Default")
      (node (ref "U31") (pin "89") (pinfunction "LED3_1_89") (pintype "bidirectional"))
    )
    (net (code "29") (name "/LED4_0") (class "Default")
      (node (ref "R174") (pin "1") (pinfunction "1_1") (pintype "passive"))
      (node (ref "U31") (pin "85") (pinfunction "LED4_0_85") (pintype "bidirectional"))
    )
    (net (code "30") (name "/LED4_1") (class "Default")
      (node (ref "R178") (pin "1") (pinfunction "1_1") (pintype "passive"))
      (node (ref "U31") (pin "86") (pinfunction "LED4_1_86") (pintype "bidirectional"))
    )
    (net (code "31") (name "/LED5_0") (class "Default")
      (node (ref "U31") (pin "102") (pinfunction "LED5_0_102") (pintype "bidirectional"))
    )
    (net (code "32") (name "/LED5_1") (class "Default")
      (node (ref "R179") (pin "1") (pinfunction "1_1") (pintype "passive"))
      (node (ref "U31") (pin "103") (pinfunction "LED5_1_103") (pintype "bidirectional"))
    )
    (net (code "33") (name "/P1_TXRXA_N") (class "Default")
      (node (ref "U31") (pin "2") (pinfunction "TXRX1M_A_2") (pintype "bidirectional"))
    )
    (net (code "34") (name "/P1_TXRXA_P") (class "Default")
      (node (ref "U31") (pin "1") (pinfunction "TXRX1P_A_1") (pintype "bidirectional"))
    )
    (net (code "35") (name "/P1_TXRXB_N") (class "Default")
      (node (ref "U31") (pin "5") (pinfunction "TXRX1M_B_5") (pintype "bidirectional"))
    )
    (net (code "36") (name "/P1_TXRXB_P") (class "Default")
      (node (ref "U31") (pin "4") (pinfunction "TXRX1P_B_4") (pintype "bidirectional"))
    )
    (net (code "37") (name "/P1_TXRXC_N") (class "Default")
      (node (ref "U31") (pin "7") (pinfunction "TXRX1M_C_7") (pintype "bidirectional"))
    )
    (net (code "38") (name "/P1_TXRXC_P") (class "Default")
      (node (ref "U31") (pin "6") (pinfunction "TXRX1P_C_6") (pintype "bidirectional"))
    )
    (net (code "39") (name "/P1_TXRXD_N") (class "Default")
      (node (ref "U31") (pin "9") (pinfunction "TXRX1M_D_9") (pintype "bidirectional"))
    )
    (net (code "40") (name "/P1_TXRXD_P") (class "Default")
      (node (ref "U31") (pin "8") (pinfunction "TXRX1P_D_8") (pintype "bidirectional"))
    )
    (net (code "41") (name "/P2_TXRXA_N") (class "Default")
      (node (ref "U31") (pin "13") (pinfunction "TXRX2M_A_13") (pintype "bidirectional"))
    )
    (net (code "42") (name "/P2_TXRXA_P") (class "Default")
      (node (ref "U31") (pin "12") (pinfunction "TXRX2P_A_12") (pintype "bidirectional"))
    )
    (net (code "43") (name "/P2_TXRXB_N") (class "Default")
      (node (ref "U31") (pin "16") (pinfunction "TXRX2M_B_16") (pintype "bidirectional"))
    )
    (net (code "44") (name "/P2_TXRXB_P") (class "Default")
      (node (ref "U31") (pin "15") (pinfunction "TXRX2P_B_15") (pintype "bidirectional"))
    )
    (net (code "45") (name "/P2_TXRXC_N") (class "Default")
      (node (ref "U31") (pin "18") (pinfunction "TXRX2M_C_18") (pintype "bidirectional"))
    )
    (net (code "46") (name "/P2_TXRXC_P") (class "Default")
      (node (ref "U31") (pin "17") (pinfunction "TXRX2P_C_17") (pintype "bidirectional"))
    )
    (net (code "47") (name "/P2_TXRXD_N") (class "Default")
      (node (ref "U31") (pin "21") (pinfunction "TXRX2M_D_21") (pintype "bidirectional"))
    )
    (net (code "48") (name "/P2_TXRXD_P") (class "Default")
      (node (ref "U31") (pin "20") (pinfunction "TXRX2P_D_20") (pintype "bidirectional"))
    )
    (net (code "49") (name "/P3_TXRXA_N") (class "Default")
      (node (ref "U31") (pin "25") (pinfunction "TXRX3M_A_25") (pintype "bidirectional"))
    )
    (net (code "50") (name "/P3_TXRXA_P") (class "Default")
      (node (ref "U31") (pin "24") (pinfunction "TXRX3P_A_24") (pintype "bidirectional"))
    )
    (net (code "51") (name "/P3_TXRXB_N") (class "Default")
      (node (ref "U31") (pin "27") (pinfunction "TXRX3M_B_27") (pintype "bidirectional"))
    )
    (net (code "52") (name "/P3_TXRXB_P") (class "Default")
      (node (ref "U31") (pin "26") (pinfunction "TXRX3P_B_26") (pintype "bidirectional"))
    )
    (net (code "53") (name "/P3_TXRXC_N") (class "Default")
      (node (ref "U31") (pin "29") (pinfunction "TXRX3M_C_29") (pintype "bidirectional"))
    )
    (net (code "54") (name "/P3_TXRXC_P") (class "Default")
      (node (ref "U31") (pin "28") (pinfunction "TXRX3P_C_28") (pintype "bidirectional"))
    )
    (net (code "55") (name "/P3_TXRXD_N") (class "Default")
      (node (ref "U31") (pin "32") (pinfunction "TXRX3M_D_32") (pintype "bidirectional"))
    )
    (net (code "56") (name "/P3_TXRXD_P") (class "Default")
      (node (ref "U31") (pin "31") (pinfunction "TXRX3P_D_31") (pintype "bidirectional"))
    )
    (net (code "57") (name "/P4_TXRXA_N") (class "Default")
      (node (ref "U31") (pin "35") (pinfunction "TXRX4M_A_35") (pintype "bidirectional"))
    )
    (net (code "58") (name "/P4_TXRXA_P") (class "Default")
      (node (ref "U31") (pin "34") (pinfunction "TXRX4P_A_34") (pintype "bidirectional"))
    )
    (net (code "59") (name "/P4_TXRXB_N") (class "Default")
      (node (ref "U31") (pin "38") (pinfunction "TXRX4M_B_38") (pintype "bidirectional"))
    )
    (net (code "60") (name "/P4_TXRXB_P") (class "Default")
      (node (ref "U31") (pin "37") (pinfunction "TXRX4P_B_37") (pintype "bidirectional"))
    )
    (net (code "61") (name "/P4_TXRXC_N") (class "Default")
      (node (ref "U31") (pin "40") (pinfunction "TXRX4M_C_40") (pintype "bidirectional"))
    )
    (net (code "62") (name "/P4_TXRXC_P") (class "Default")
      (node (ref "U31") (pin "39") (pinfunction "TXRX4P_C_39") (pintype "bidirectional"))
    )
    (net (code "63") (name "/P4_TXRXD_N") (class "Default")
      (node (ref "U31") (pin "43") (pinfunction "TXRX4M_D_43") (pintype "bidirectional"))
    )
    (net (code "64") (name "/P4_TXRXD_P") (class "Default")
      (node (ref "U31") (pin "42") (pinfunction "TXRX4P_D_42") (pintype "bidirectional"))
    )
    (net (code "65") (name "/P5_TXRXA_N") (class "Default")
      (node (ref "U31") (pin "113") (pinfunction "TXRX5M_A_113") (pintype "bidirectional"))
    )
    (net (code "66") (name "/P5_TXRXA_P") (class "Default")
      (node (ref "U31") (pin "112") (pinfunction "TXRX5P_A_112") (pintype "bidirectional"))
    )
    (net (code "67") (name "/P5_TXRXB_N") (class "Default")
      (node (ref "U31") (pin "116") (pinfunction "TXRX5M_B_116") (pintype "bidirectional"))
    )
    (net (code "68") (name "/P5_TXRXB_P") (class "Default")
      (node (ref "U31") (pin "115") (pinfunction "TXRX5P_B_115") (pintype "bidirectional"))
    )
    (net (code "69") (name "/P5_TXRXC_N") (class "Default")
      (node (ref "U31") (pin "118") (pinfunction "TXRX5M_C_118") (pintype "bidirectional"))
    )
    (net (code "70") (name "/P5_TXRXC_P") (class "Default")
      (node (ref "U31") (pin "117") (pinfunction "TXRX5P_C_117") (pintype "bidirectional"))
    )
    (net (code "71") (name "/P5_TXRXD_N") (class "Default")
      (node (ref "U31") (pin "121") (pinfunction "TXRX5M_D_121") (pintype "bidirectional"))
    )
    (net (code "72") (name "/P5_TXRXD_P") (class "Default")
      (node (ref "U31") (pin "120") (pinfunction "TXRX5P_D_120") (pintype "bidirectional"))
    )
    (net (code "73") (name "/PME_N") (class "Default")
      (node (ref "R162") (pin "2") (pinfunction "2_2") (pintype "passive"))
      (node (ref "U31") (pin "93") (pinfunction "PME_N_93") (pintype "output"))
    )
    (net (code "74") (name "/RESET_B") (class "Default")
      (node (ref "U33") (pin "2") (pinfunction "B_2") (pintype "input"))
    )
    (net (code "75") (name "/SW_RESETN") (class "Default")
      (node (ref "U31") (pin "96") (pinfunction "RESET_N_96") (pintype "input"))
      (node (ref "U33") (pin "4") (pinfunction "Y_4") (pintype "output"))
    )
    (net (code "76") (name "/SYNCLKO") (class "Default")
      (node (ref "R167") (pin "2") (pinfunction "2_2") (pintype "passive"))
      (node (ref "R182") (pin "1") (pinfunction "1_1") (pintype "passive"))
    )
    (net (code "77") (name "/SYNCLKO_ZYNQ") (class "Default")
      (node (ref "R181") (pin "2") (pinfunction "2_2") (pintype "passive"))
      (node (ref "R182") (pin "2") (pinfunction "2_2") (pintype "passive"))
    )
    (net (code "78") (name "/XI") (class "Default")
      (node (ref "C257") (pin "2") (pinfunction "2_2") (pintype "passive"))
      (node (ref "U31") (pin "126") (pinfunction "XI_126") (pintype "input"))
      (node (ref "Y1") (pin "3") (pinfunction "Osc2_3") (pintype "passive"))
    )
    (net (code "79") (name "/XO") (class "Default")
      (node (ref "R168") (pin "1") (pinfunction "1_1") (pintype "passive"))
      (node (ref "U31") (pin "125") (pinfunction "X0_125") (pintype "output"))
    )
    (net (code "80") (name "1V2_ETH") (class "Default")
      (node (ref "C224") (pin "2") (pinfunction "2_2") (pintype "passive"))
      (node (ref "C225") (pin "2") (pinfunction "2_2") (pintype "passive"))
      (node (ref "C226") (pin "2") (pinfunction "2_2") (pintype "passive"))
      (node (ref "C227") (pin "2") (pinfunction "2_2") (pintype "passive"))
      (node (ref "C259") (pin "2") (pinfunction "2_2") (pintype "passive"))
      (node (ref "C260") (pin "2") (pinfunction "2_2") (pintype "passive"))
      (node (ref "C261") (pin "2") (pinfunction "2_2") (pintype "passive"))
      (node (ref "C262") (pin "2") (pinfunction "2_2") (pintype "passive"))
      (node (ref "C263") (pin "2") (pinfunction "2_2") (pintype "passive"))
      (node (ref "C264") (pin "2") (pinfunction "2_2") (pintype "passive"))
      (node (ref "C265") (pin "2") (pinfunction "2_2") (pintype "passive"))
      (node (ref "C266") (pin "2") (pinfunction "2_2") (pintype "passive"))
      (node (ref "C267") (pin "2") (pinfunction "2_2") (pintype "passive"))
      (node (ref "C268") (pin "2") (pinfunction "2_2") (pintype "passive"))
      (node (ref "FB17") (pin "1") (pinfunction "1_1") (pintype "passive"))
      (node (ref "FB20") (pin "1") (pinfunction "1_1") (pintype "passive"))
      (node (ref "L1") (pin "2") (pinfunction "F_2") (pintype "passive"))
      (node (ref "R148") (pin "2") (pinfunction "2_2") (pintype "passive"))
      (node (ref "TP1") (pin "1") (pinfunction "P1_1") (pintype "passive"))
      (node (ref "U31") (pin "104") (pinfunction "DVDDL_104") (pintype "power_in"))
      (node (ref "U31") (pin "11") (pinfunction "DVDDL_11") (pintype "power_in"))
      (node (ref "U31") (pin "110") (pinfunction "DVDDL_110") (pintype "power_in"))
      (node (ref "U31") (pin "23") (pinfunction "DVDDL_23") (pintype "power_in"))
      (node (ref "U31") (pin "45") (pinfunction "DVDDL_45") (pintype "power_in"))
      (node (ref "U31") (pin "56") (pinfunction "DVDDL_56") (pintype "power_in"))
      (node (ref "U31") (pin "66") (pinfunction "DVDDL_66") (pintype "power_in"))
      (node (ref "U31") (pin "70") (pinfunction "DVDDL_70") (pintype "power_in"))
      (node (ref "U31") (pin "87") (pinfunction "DVDDL_87") (pintype "power_in"))
      (node (ref "U32") (pin "5") (pinfunction "SNS_5") (pintype "passive"))
    )
    (net (code "81") (name "2V5_ETH") (class "Default")
      (node (ref "FB18") (pin "1") (pinfunction "1_1") (pintype "passive"))
      (node (ref "FB19") (pin "1") (pinfunction "1_1") (pintype "passive"))
      (node (ref "R170") (pin "2") (pinfunction "2_2") (pintype "passive"))
    )
    (net (code "82") (name "AVDDH2v5") (class "Default")
      (node (ref "C247") (pin "2") (pinfunction "2_2") (pintype "passive"))
      (node (ref "C248") (pin "2") (pinfunction "2_2") (pintype "passive"))
      (node (ref "C249") (pin "2") (pinfunction "2_2") (pintype "passive"))
      (node (ref "C250") (pin "2") (pinfunction "2_2") (pintype "passive"))
      (node (ref "C251") (pin "2") (pinfunction "2_2") (pintype "passive"))
      (node (ref "C252") (pin "2") (pinfunction "2_2") (pintype "passive"))
      (node (ref "C253") (pin "2") (pinfunction "2_2") (pintype "passive"))
      (node (ref "C271") (pin "2") (pinfunction "2_2") (pintype "passive"))
      (node (ref "FB19") (pin "2") (pinfunction "2_2") (pintype "passive"))
      (node (ref "U31") (pin "10") (pinfunction "AVDDH_10") (pintype "power_in"))
      (node (ref "U31") (pin "111") (pinfunction "AVDDH_111") (pintype "power_in"))
      (node (ref "U31") (pin "122") (pinfunction "AVDDH_122") (pintype "power_in"))
      (node (ref "U31") (pin "128") (pinfunction "AVDDH_128") (pintype "power_in"))
      (node (ref "U31") (pin "22") (pinfunction "AVDDH_22") (pintype "power_in"))
      (node (ref "U31") (pin "33") (pinfunction "AVDDH_33") (pintype "power_in"))
      (node (ref "U31") (pin "44") (pinfunction "AVDDH_44") (pintype "power_in"))
    )
    (net (code "83") (name "AVDDL1v2") (class "Default")
      (node (ref "C233") (pin "2") (pinfunction "2_2") (pintype "passive"))
      (node (ref "C234") (pin "2") (pinfunction "2_2") (pintype "passive"))
      (node (ref "C235") (pin "2") (pinfunction "2_2") (pintype "passive"))
      (node (ref "C236") (pin "2") (pinfunction "2_2") (pintype "passive"))
      (node (ref "C237") (pin "2") (pinfunction "2_2") (pintype "passive"))
      (node (ref "C238") (pin "2") (pinfunction "2_2") (pintype "passive"))
      (node (ref "C239") (pin "2") (pinfunction "2_2") (pintype "passive"))
      (node (ref "C240") (pin "2") (pinfunction "2_2") (pintype "passive"))
      (node (ref "C241") (pin "2") (pinfunction "2_2") (pintype "passive"))
      (node (ref "C242") (pin "2") (pinfunction "2_2") (pintype "passive"))
      (node (ref "C272") (pin "2") (pinfunction "2_2") (pintype "passive"))
      (node (ref "FB20") (pin "2") (pinfunction "2_2") (pintype "passive"))
      (node (ref "U31") (pin "114") (pinfunction "AVDDL_114") (pintype "power_in"))
      (node (ref "U31") (pin "119") (pinfunction "AVDDL_119") (pintype "power_in"))
      (node (ref "U31") (pin "124") (pinfunction "AVDDL_124") (pintype "power_in"))
      (node (ref "U31") (pin "14") (pinfunction "AVDDL_14") (pintype "power_in"))
      (node (ref "U31") (pin "19") (pinfunction "AVDDL_19") (pintype "power_in"))
      (node (ref "U31") (pin "3") (pinfunction "AVDDL_3") (pintype "power_in"))
      (node (ref "U31") (pin "30") (pinfunction "AVDDL_30") (pintype "power_in"))
      (node (ref "U31") (pin "36") (pinfunction "AVDDL_36") (pintype "power_in"))
      (node (ref "U31") (pin "41") (pinfunction "AVDDL_41") (pintype "power_in"))
    )
    (net (code "84") (name "GND") (class "Default")
      (node (ref "C223") (pin "1") (pinfunction "1_1") (pintype "passive"))
      (node (ref "C225") (pin "1") (pinfunction "1_1") (pintype "passive"))
      (node (ref "C226") (pin "1") (pinfunction "1_1") (pintype "passive"))
      (node (ref "C227") (pin "1") (pinfunction "1_1") (pintype "passive"))
      (node (ref "C228") (pin "2") (pinfunction "2_2") (pintype "passive"))
      (node (ref "C229") (pin "1") (pinfunction "1_1") (pintype "passive"))
      (node (ref "C230") (pin "1") (pinfunction "1_1") (pintype "passive"))
      (node (ref "C231") (pin "2") (pinfunction "2_2") (pintype "passive"))
      (node (ref "C232") (pin "2") (pinfunction "2_2") (pintype "passive"))
      (node (ref "C233") (pin "1") (pinfunction "1_1") (pintype "passive"))
      (node (ref "C234") (pin "1") (pinfunction "1_1") (pintype "passive"))
      (node (ref "C235") (pin "1") (pinfunction "1_1") (pintype "passive"))
      (node (ref "C236") (pin "1") (pinfunction "1_1") (pintype "passive"))
      (node (ref "C237") (pin "1") (pinfunction "1_1") (pintype "passive"))
      (node (ref "C238") (pin "1") (pinfunction "1_1") (pintype "passive"))
      (node (ref "C239") (pin "1") (pinfunction "1_1") (pintype "passive"))
      (node (ref "C240") (pin "1") (pinfunction "1_1") (pintype "passive"))
      (node (ref "C241") (pin "1") (pinfunction "1_1") (pintype "passive"))
      (node (ref "C242") (pin "1") (pinfunction "1_1") (pintype "passive"))
      (node (ref "C243") (pin "1") (pinfunction "1_1") (pintype "passive"))
      (node (ref "C244") (pin "1") (pinfunction "1_1") (pintype "passive"))
      (node (ref "C245") (pin "1") (pinfunction "1_1") (pintype "passive"))
      (node (ref "C246") (pin "1") (pinfunction "1_1") (pintype "passive"))
      (node (ref "C247") (pin "1") (pinfunction "1_1") (pintype "passive"))
      (node (ref "C248") (pin "1") (pinfunction "1_1") (pintype "passive"))
      (node (ref "C249") (pin "1") (pinfunction "1_1") (pintype "passive"))
      (node (ref "C250") (pin "1") (pinfunction "1_1") (pintype "passive"))
      (node (ref "C251") (pin "1") (pinfunction "1_1") (pintype "passive"))
      (node (ref "C252") (pin "1") (pinfunction "1_1") (pintype "passive"))
      (node (ref "C253") (pin "1") (pinfunction "1_1") (pintype "passive"))
      (node (ref "C254") (pin "1") (pinfunction "1_1") (pintype "passive"))
      (node (ref "C255") (pin "1") (pinfunction "1_1") (pintype "passive"))
      (node (ref "C256") (pin "1") (pinfunction "1_1") (pintype "passive"))
      (node (ref "C257") (pin "1") (pinfunction "1_1") (pintype "passive"))
      (node (ref "C258") (pin "1") (pinfunction "1_1") (pintype "passive"))
      (node (ref "C259") (pin "1") (pinfunction "1_1") (pintype "passive"))
      (node (ref "C260") (pin "1") (pinfunction "1_1") (pintype "passive"))
      (node (ref "C261") (pin "1") (pinfunction "1_1") (pintype "passive"))
      (node (ref "C262") (pin "1") (pinfunction "1_1") (pintype "passive"))
      (node (ref "C263") (pin "1") (pinfunction "1_1") (pintype "passive"))
      (node (ref "C264") (pin "1") (pinfunction "1_1") (pintype "passive"))
      (node (ref "C265") (pin "1") (pinfunction "1_1") (pintype "passive"))
      (node (ref "C266") (pin "1") (pinfunction "1_1") (pintype "passive"))
      (node (ref "C267") (pin "1") (pinfunction "1_1") (pintype "passive"))
      (node (ref "C268") (pin "1") (pinfunction "1_1") (pintype "passive"))
      (node (ref "C269") (pin "1") (pinfunction "1_1") (pintype "passive"))
      (node (ref "C270") (pin "1") (pinfunction "1_1") (pintype "passive"))
      (node (ref "C271") (pin "1") (pinfunction "1_1") (pintype "passive"))
      (node (ref "C272") (pin "1") (pinfunction "1_1") (pintype "passive"))
      (node (ref "C273") (pin "1") (pinfunction "1_1") (pintype "passive"))
      (node (ref "OSC1") (pin "3") (pinfunction "GND_3") (pintype "passive"))
      (node (ref "R149") (pin "1") (pinfunction "1_1") (pintype "passive"))
      (node (ref "R156") (pin "2") (pinfunction "2_2") (pintype "passive"))
      (node (ref "R157") (pin "2") (pinfunction "2_2") (pintype "passive"))
      (node (ref "R158") (pin "2") (pinfunction "2_2") (pintype "passive"))
      (node (ref "R159") (pin "2") (pinfunction "2_2") (pintype "passive"))
      (node (ref "R161") (pin "2") (pinfunction "2_2") (pintype "passive"))
      (node (ref "R169") (pin "1") (pinfunction "1_1") (pintype "passive"))
      (node (ref "R171") (pin "2") (pinfunction "2_2") (pintype "passive"))
      (node (ref "SW1") (pin "10") (pinfunction "10_10") (pintype "passive"))
      (node (ref "SW1") (pin "11") (pinfunction "11_11") (pintype "passive"))
      (node (ref "SW1") (pin "12") (pinfunction "12_12") (pintype "passive"))
      (node (ref "SW1") (pin "13") (pinfunction "13_13") (pintype "passive"))
      (node (ref "SW1") (pin "14") (pinfunction "14_14") (pintype "passive"))
      (node (ref "SW1") (pin "15") (pinfunction "15_15") (pintype "passive"))
      (node (ref "SW1") (pin "9") (pinfunction "9_9") (pintype "passive"))
      (node (ref "U31") (pin "107") (pinfunction "GND_107") (pintype "power_in"))
      (node (ref "U31") (pin "109") (pinfunction "GND_109") (pintype "power_in"))
      (node (ref "U31") (pin "123") (pinfunction "GND_123") (pintype "power_in"))
      (node (ref "U31") (pin "46") (pinfunction "GND_46") (pintype "power_in"))
      (node (ref "U31") (pin "47") (pinfunction "GND_47") (pintype "power_in"))
      (node (ref "U31") (pin "69") (pinfunction "GND_69") (pintype "power_in"))
      (node (ref "U31") (pin "75") (pinfunction "GND_75") (pintype "power_in"))
      (node (ref "U31") (pin "77") (pinfunction "GND_77") (pintype "power_in"))
      (node (ref "U31") (pin "80") (pinfunction "GND_80") (pintype "power_in"))
      (node (ref "U31") (pin "EP") (pinfunction "ePAD_EP") (pintype "power_in"))
      (node (ref "U32") (pin "12") (pinfunction "PGND_12") (pintype "power_in"))
      (node (ref "U32") (pin "13") (pinfunction "EP_13") (pintype "passive"))
      (node (ref "U32") (pin "8") (pinfunction "AGND_8") (pintype "power_in"))
      (node (ref "U33") (pin "3") (pinfunction "GND_3") (pintype "power_in"))
      (node (ref "Y1") (pin "2") (pinfunction "GND_2") (pintype "power_in"))
    )
    (net (code "85") (name "Net-(J20-P2)") (class "Default")
      (node (ref "J20") (pin "2") (pinfunction "P2_2") (pintype "passive"))
      (node (ref "R172") (pin "2") (pinfunction "2_2") (pintype "passive"))
    )
    (net (code "86") (name "Net-(OSC1-EN)") (class "Default")
      (node (ref "OSC1") (pin "1") (pinfunction "EN_1") (pintype "input"))
      (node (ref "R180") (pin "1") (pinfunction "1_1") (pintype "passive"))
    )
    (net (code "87") (name "Net-(OSC1-OUT)") (class "Default")
      (node (ref "OSC1") (pin "4") (pinfunction "OUT_4") (pintype "output"))
      (node (ref "R181") (pin "1") (pinfunction "1_1") (pintype "passive"))
    )
    (net (code "88") (name "Net-(R170-Pad1)") (class "Default")
      (node (ref "R170") (pin "1") (pinfunction "1_1") (pintype "passive"))
      (node (ref "R171") (pin "1") (pinfunction "1_1") (pintype "passive"))
      (node (ref "Y1") (pin "4") (pinfunction "GND_4") (pintype "power_in"))
    )
    (net (code "89") (name "Net-(R173-Pad2)") (class "Default")
      (node (ref "R173") (pin "2") (pinfunction "2_2") (pintype "passive"))
      (node (ref "SW1") (pin "2") (pinfunction "2_2") (pintype "passive"))
    )
    (net (code "90") (name "Net-(R174-Pad2)") (class "Default")
      (node (ref "R174") (pin "2") (pinfunction "2_2") (pintype "passive"))
      (node (ref "SW1") (pin "3") (pinfunction "3_3") (pintype "passive"))
    )
    (net (code "91") (name "Net-(R175-Pad2)") (class "Default")
      (node (ref "R175") (pin "2") (pinfunction "2_2") (pintype "passive"))
      (node (ref "SW1") (pin "4") (pinfunction "4_4") (pintype "passive"))
    )
    (net (code "92") (name "Net-(R176-Pad2)") (class "Default")
      (node (ref "R176") (pin "2") (pinfunction "2_2") (pintype "passive"))
      (node (ref "SW1") (pin "5") (pinfunction "5_5") (pintype "passive"))
    )
    (net (code "93") (name "Net-(R177-Pad2)") (class "Default")
      (node (ref "R177") (pin "2") (pinfunction "2_2") (pintype "passive"))
      (node (ref "SW1") (pin "6") (pinfunction "6_6") (pintype "passive"))
    )
    (net (code "94") (name "Net-(R178-Pad2)") (class "Default")
      (node (ref "R178") (pin "2") (pinfunction "2_2") (pintype "passive"))
      (node (ref "SW1") (pin "7") (pinfunction "7_7") (pintype "passive"))
    )
    (net (code "95") (name "Net-(R179-Pad2)") (class "Default")
      (node (ref "R179") (pin "2") (pinfunction "2_2") (pintype "passive"))
      (node (ref "SW1") (pin "8") (pinfunction "8_8") (pintype "passive"))
    )
    (net (code "96") (name "Net-(U31A-RXD6_0)") (class "Default")
      (node (ref "R155") (pin "1") (pinfunction "1_1") (pintype "passive"))
      (node (ref "U31") (pin "65") (pinfunction "RXD6_0_65") (pintype "bidirectional"))
    )
    (net (code "97") (name "Net-(U31A-RXD6_1)") (class "Default")
      (node (ref "R154") (pin "1") (pinfunction "1_1") (pintype "passive"))
      (node (ref "U31") (pin "64") (pinfunction "RXD6_1_64") (pintype "bidirectional"))
    )
    (net (code "98") (name "Net-(U31A-RXD6_2)") (class "Default")
      (node (ref "R153") (pin "1") (pinfunction "1_1") (pintype "passive"))
      (node (ref "U31") (pin "63") (pinfunction "RXD6_2_63") (pintype "bidirectional"))
    )
    (net (code "99") (name "Net-(U31A-RXD6_3)") (class "Default")
      (node (ref "R152") (pin "1") (pinfunction "1_1") (pintype "passive"))
      (node (ref "U31") (pin "62") (pinfunction "RXD6_3_62") (pintype "bidirectional"))
    )
    (net (code "100") (name "Net-(U31A-RX_CLK6{slash}REFCLKO6)") (class "Default")
      (node (ref "R150") (pin "1") (pinfunction "1_1") (pintype "passive"))
      (node (ref "U31") (pin "57") (pinfunction "RX_CLK6/REFCLKO6_57") (pintype "bidirectional"))
    )
    (net (code "101") (name "Net-(U31A-RX_DV6{slash}CRS_DV6{slash}RX_CTL6)") (class "Default")
      (node (ref "R151") (pin "1") (pinfunction "1_1") (pintype "passive"))
      (node (ref "U31") (pin "58") (pinfunction "RX_DV6/CRS_DV6/RX_CTL6_58") (pintype "bidirectional"))
    )
    (net (code "102") (name "Net-(U31A-SYNCLKO)") (class "Default")
      (node (ref "R167") (pin "1") (pinfunction "1_1") (pintype "passive"))
      (node (ref "U31") (pin "95") (pinfunction "SYNCLKO_95") (pintype "bidirectional"))
    )
    (net (code "103") (name "Net-(U31A-S_REXT)") (class "Default")
      (node (ref "R161") (pin "1") (pinfunction "1_1") (pintype "passive"))
      (node (ref "U31") (pin "76") (pinfunction "S_REXT_76") (pintype "bidirectional"))
    )
    (net (code "104") (name "Net-(U32-AVIN)") (class "Default")
      (node (ref "C230") (pin "2") (pinfunction "2_2") (pintype "passive"))
      (node (ref "C231") (pin "1") (pinfunction "1_1") (pintype "passive"))
      (node (ref "R146") (pin "1") (pinfunction "1_1") (pintype "passive"))
      (node (ref "U32") (pin "9") (pinfunction "AVIN_9") (pintype "power_in"))
    )
    (net (code "105") (name "Net-(U32-EN)") (class "Default")
      (node (ref "C228") (pin "1") (pinfunction "1_1") (pintype "passive"))
      (node (ref "R147") (pin "1") (pinfunction "1_1") (pintype "passive"))
      (node (ref "U32") (pin "4") (pinfunction "EN_4") (pintype "input"))
    )
    (net (code "106") (name "Net-(U32-FB)") (class "Default")
      (node (ref "C224") (pin "1") (pinfunction "1_1") (pintype "passive"))
      (node (ref "R148") (pin "1") (pinfunction "1_1") (pintype "passive"))
      (node (ref "R149") (pin "2") (pinfunction "2_2") (pintype "passive"))
      (node (ref "U32") (pin "6") (pinfunction "FB_6") (pintype "tri_state"))
    )
    (net (code "107") (name "Net-(U32-SS)") (class "Default")
      (node (ref "C229") (pin "2") (pinfunction "2_2") (pintype "passive"))
      (node (ref "U32") (pin "7") (pinfunction "SS_7") (pintype "passive"))
    )
    (net (code "108") (name "Net-(Y1-Osc1)") (class "Default")
      (node (ref "C258") (pin "2") (pinfunction "2_2") (pintype "passive"))
      (node (ref "R168") (pin "2") (pinfunction "2_2") (pintype "passive"))
      (node (ref "Y1") (pin "1") (pinfunction "Osc1_1") (pintype "passive"))
    )
    (net (code "109") (name "VDDHS2v5") (class "Default")
      (node (ref "C245") (pin "2") (pinfunction "2_2") (pintype "passive"))
      (node (ref "C246") (pin "2") (pinfunction "2_2") (pintype "passive"))
      (node (ref "C270") (pin "2") (pinfunction "2_2") (pintype "passive"))
      (node (ref "FB18") (pin "2") (pinfunction "2_2") (pintype "passive"))
      (node (ref "U31") (pin "72") (pinfunction "VDDHS_72") (pintype "power_in"))
      (node (ref "U31") (pin "83") (pinfunction "VDDHS_83") (pintype "power_in"))
    )
    (net (code "110") (name "VDDLS1v2") (class "Default")
      (node (ref "C243") (pin "2") (pinfunction "2_2") (pintype "passive"))
      (node (ref "C244") (pin "2") (pinfunction "2_2") (pintype "passive"))
      (node (ref "C269") (pin "2") (pinfunction "2_2") (pintype "passive"))
      (node (ref "FB17") (pin "2") (pinfunction "2_2") (pintype "passive"))
      (node (ref "U31") (pin "71") (pinfunction "VDDLS_71") (pintype "power_in"))
      (node (ref "U31") (pin "84") (pinfunction "VDDLS_84") (pintype "power_in"))
    )
    (net (code "111") (name "unconnected-(OSC1-NC-Pad2)") (class "Default")
      (node (ref "OSC1") (pin "2") (pinfunction "NC_2") (pintype "passive+no_connect"))
    )
    (net (code "112") (name "unconnected-(OSC1-NC-Pad5)") (class "Default")
      (node (ref "OSC1") (pin "5") (pinfunction "NC_5") (pintype "passive+no_connect"))
    )
    (net (code "113") (name "unconnected-(U31A-COL6-Pad51)") (class "Default")
      (node (ref "U31") (pin "51") (pinfunction "COL6_51") (pintype "bidirectional+no_connect"))
    )
    (net (code "114") (name "unconnected-(U31A-CRS6-Pad60)") (class "Default")
      (node (ref "U31") (pin "60") (pinfunction "CRS6_60") (pintype "bidirectional+no_connect"))
    )
    (net (code "115") (name "unconnected-(U31A-GPIO_1-Pad90)") (class "Default")
      (node (ref "U31") (pin "90") (pinfunction "GPIO_1_90") (pintype "bidirectional+no_connect"))
    )
    (net (code "116") (name "unconnected-(U31A-RX_ER6-Pad59)") (class "Default")
      (node (ref "U31") (pin "59") (pinfunction "RX_ER6_59") (pintype "bidirectional+no_connect"))
    )
    (net (code "117") (name "unconnected-(U31A-S_IN7M-Pad78)") (class "Default")
      (node (ref "U31") (pin "78") (pinfunction "S_IN7M_78") (pintype "input+no_connect"))
    )
    (net (code "118") (name "unconnected-(U31A-S_IN7P-Pad79)") (class "Default")
      (node (ref "U31") (pin "79") (pinfunction "S_IN7P_79") (pintype "input+no_connect"))
    )
    (net (code "119") (name "unconnected-(U31A-S_OUT7M-Pad82)") (class "Default")
      (node (ref "U31") (pin "82") (pinfunction "S_OUT7M_82") (pintype "output+no_connect"))
    )
    (net (code "120") (name "unconnected-(U31A-S_OUT7P-Pad81)") (class "Default")
      (node (ref "U31") (pin "81") (pinfunction "S_OUT7P_81") (pintype "output+no_connect"))
    )
    (net (code "121") (name "unconnected-(U31A-S_REFCLKM-Pad74)") (class "Default")
      (node (ref "U31") (pin "74") (pinfunction "S_REFCLKM_74") (pintype "input+no_connect"))
    )
    (net (code "122") (name "unconnected-(U31A-S_REFCLKP-Pad73)") (class "Default")
      (node (ref "U31") (pin "73") (pinfunction "S_REFCLKP_73") (pintype "input+no_connect"))
    )
    (net (code "123") (name "unconnected-(U31A-TX_ER6-Pad50)") (class "Default")
      (node (ref "U31") (pin "50") (pinfunction "TX_ER6_50") (pintype "input+no_connect"))
    )
    (net (code "124") (name "unconnected-(U31B-NC-Pad108)") (class "Default")
      (node (ref "U31") (pin "108") (pinfunction "NC_108") (pintype "passive+no_connect"))
    )
    (net (code "125") (name "unconnected-(U32-PG-Pad3)") (class "Default")
      (node (ref "U32") (pin "3") (pinfunction "PG_3") (pintype "power_in+no_connect"))
    )
  )
)
